# Serial.net
KiCad netlist of a schematic drawn in Altium Designer
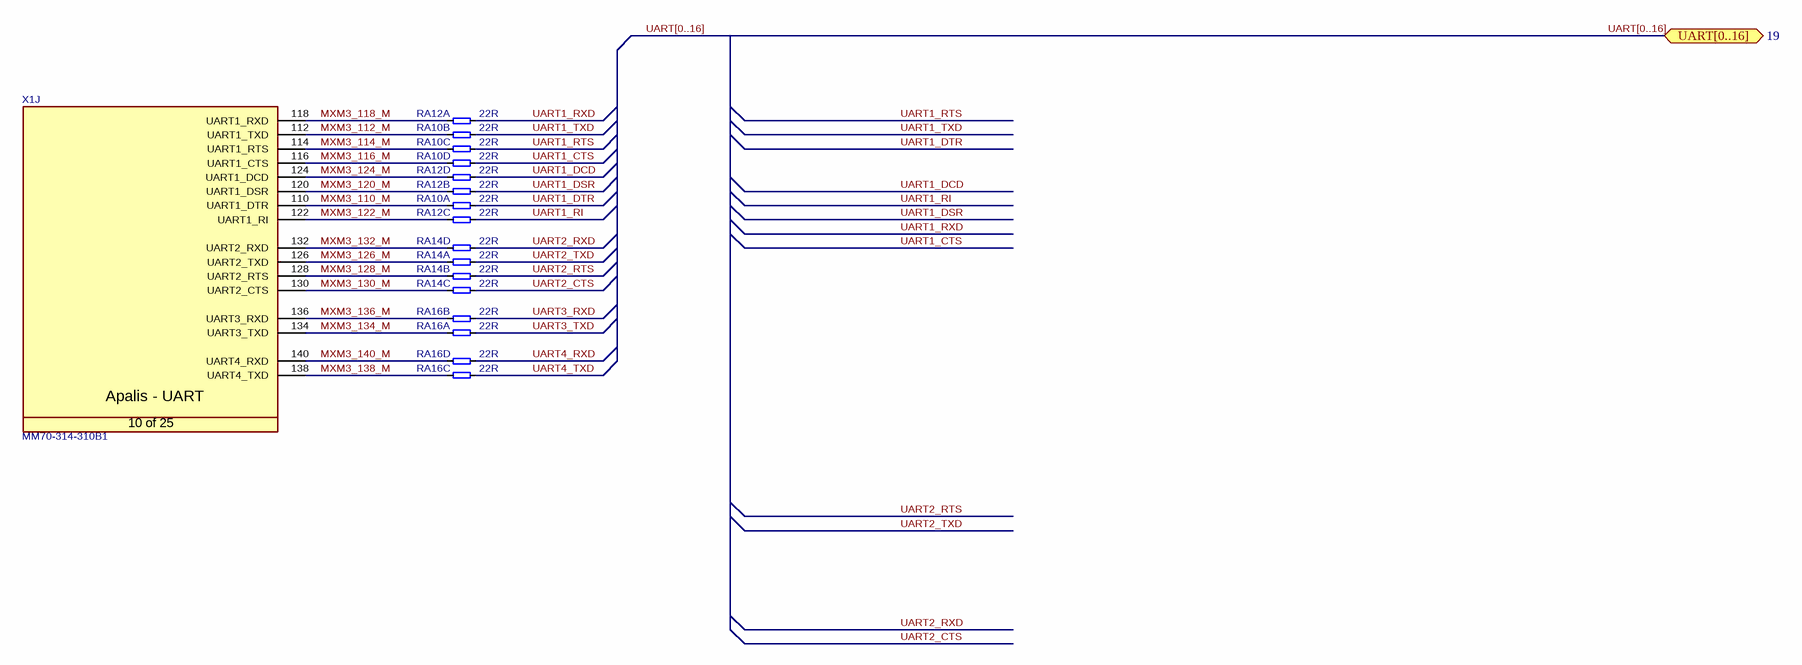
[diagram p0: Serial.SchDoc]

(export (version "E")
  (design (tool "Eeschema 10.0.6"))
  (components
    (comp (ref "RA10")
      (value "22R")
      (footprint "T_Resistor_Array_X4")
      (description "Resistor Array 22 R 63mW 5% 1206")
      (fields (field (name "TOLERANCE") "5%"))
      (libsource (lib "Ixora") (part "RA-22R-63mW-5%-1206-div"))
    )
    (comp (ref "RA12")
      (value "22R")
      (footprint "T_Resistor_Array_X4")
      (description "Resistor Array 22 R 63mW 5% 1206")
      (fields (field (name "TOLERANCE") "5%"))
      (libsource (lib "Ixora") (part "RA-22R-63mW-5%-1206-div"))
    )
    (comp (ref "RA14")
      (value "22R")
      (footprint "T_Resistor_Array_X4")
      (description "Resistor Array 22 R 63mW 5% 1206")
      (fields (field (name "TOLERANCE") "5%"))
      (libsource (lib "Ixora") (part "RA-22R-63mW-5%-1206-div"))
    )
    (comp (ref "RA16")
      (value "22R")
      (footprint "T_Resistor_Array_X4")
      (description "Resistor Array 22 R 63mW 5% 1206")
      (fields (field (name "TOLERANCE") "5%"))
      (libsource (lib "Ixora") (part "RA-22R-63mW-5%-1206-div"))
    )
    (comp (ref "X1")
      (value "CON-JAE-MM70-314-310B1-314-0.5mm")
      (footprint "T_JAE_MM70-314-310B1")
      (description "MXM3 Connector")
      (fields (field (name "MANUFACTURER PART NO.") "MM70-314-310B1"))
      (libsource (lib "Ixora") (part "CON-JAE-MM70-314-310B1-314-0.5mm"))
    )
  )
  (nets
    (net (code "18") (name "/MXM3_110_M") (class "Default")
      (node (ref "RA10") (pin "1") (pinfunction "1_1") (pintype "passive"))
      (node (ref "X1") (pin "110") (pinfunction "UART1_DTR_110") (pintype "passive"))
    )
    (net (code "19") (name "/MXM3_112_M") (class "Default")
      (node (ref "RA10") (pin "2") (pinfunction "2_2") (pintype "passive"))
      (node (ref "X1") (pin "112") (pinfunction "UART1_TXD_112") (pintype "passive"))
    )
    (net (code "20") (name "/MXM3_114_M") (class "Default")
      (node (ref "RA10") (pin "3") (pinfunction "3_3") (pintype "passive"))
      (node (ref "X1") (pin "114") (pinfunction "UART1_RTS_114") (pintype "passive"))
    )
    (net (code "21") (name "/MXM3_116_M") (class "Default")
      (node (ref "RA10") (pin "4") (pinfunction "4_4") (pintype "passive"))
      (node (ref "X1") (pin "116") (pinfunction "UART1_CTS_116") (pintype "passive"))
    )
    (net (code "23") (name "/MXM3_118_M") (class "Default")
      (node (ref "RA12") (pin "1") (pinfunction "1_1") (pintype "passive"))
      (node (ref "X1") (pin "118") (pinfunction "UART1_RXD_118") (pintype "passive"))
    )
    (net (code "24") (name "/MXM3_120_M") (class "Default")
      (node (ref "RA12") (pin "2") (pinfunction "2_2") (pintype "passive"))
      (node (ref "X1") (pin "120") (pinfunction "UART1_DSR_120") (pintype "passive"))
    )
    (net (code "25") (name "/MXM3_122_M") (class "Default")
      (node (ref "RA12") (pin "3") (pinfunction "3_3") (pintype "passive"))
      (node (ref "X1") (pin "122") (pinfunction "UART1_RI_122") (pintype "passive"))
    )
    (net (code "26") (name "/MXM3_124_M") (class "Default")
      (node (ref "RA12") (pin "4") (pinfunction "4_4") (pintype "passive"))
      (node (ref "X1") (pin "124") (pinfunction "UART1_DCD_124") (pintype "passive"))
    )
    (net (code "27") (name "/MXM3_126_M") (class "Default")
      (node (ref "RA14") (pin "1") (pinfunction "1_1") (pintype "passive"))
      (node (ref "X1") (pin "126") (pinfunction "UART2_TXD_126") (pintype "passive"))
    )
    (net (code "28") (name "/MXM3_128_M") (class "Default")
      (node (ref "RA14") (pin "2") (pinfunction "2_2") (pintype "passive"))
      (node (ref "X1") (pin "128") (pinfunction "UART2_RTS_128") (pintype "passive"))
    )
    (net (code "29") (name "/MXM3_130_M") (class "Default")
      (node (ref "RA14") (pin "3") (pinfunction "3_3") (pintype "passive"))
      (node (ref "X1") (pin "130") (pinfunction "UART2_CTS_130") (pintype "passive"))
    )
    (net (code "30") (name "/MXM3_132_M") (class "Default")
      (node (ref "RA14") (pin "4") (pinfunction "4_4") (pintype "passive"))
      (node (ref "X1") (pin "132") (pinfunction "UART2_RXD_132") (pintype "passive"))
    )
    (net (code "31") (name "/MXM3_134_M") (class "Default")
      (node (ref "RA16") (pin "1") (pinfunction "1_1") (pintype "passive"))
      (node (ref "X1") (pin "134") (pinfunction "UART3_TXD_134") (pintype "passive"))
    )
    (net (code "33") (name "/MXM3_136_M") (class "Default")
      (node (ref "RA16") (pin "2") (pinfunction "2_2") (pintype "passive"))
      (node (ref "X1") (pin "136") (pinfunction "UART3_RXD_136") (pintype "passive"))
    )
    (net (code "34") (name "/MXM3_138_M") (class "Default")
      (node (ref "RA16") (pin "3") (pinfunction "3_3") (pintype "passive"))
      (node (ref "X1") (pin "138") (pinfunction "UART4_TXD_138") (pintype "passive"))
    )
    (net (code "35") (name "/MXM3_140_M") (class "Default")
      (node (ref "RA16") (pin "4") (pinfunction "4_4") (pintype "passive"))
      (node (ref "X1") (pin "140") (pinfunction "UART4_RXD_140") (pintype "passive"))
    )
    (net (code "36") (name "/UART1_CTS") (class "Default")
      (node (ref "RA10") (pin "8") (pinfunction "8_8") (pintype "passive"))
    )
    (net (code "37") (name "/UART1_DCD") (class "Default")
      (node (ref "RA12") (pin "8") (pinfunction "8_8") (pintype "passive"))
    )
    (net (code "38") (name "/UART1_DSR") (class "Default")
      (node (ref "RA12") (pin "6") (pinfunction "6_6") (pintype "passive"))
    )
    (net (code "39") (name "/UART1_DTR") (class "Default")
      (node (ref "RA10") (pin "5") (pinfunction "5_5") (pintype "passive"))
    )
    (net (code "40") (name "/UART1_RI") (class "Default")
      (node (ref "RA12") (pin "7") (pinfunction "7_7") (pintype "passive"))
    )
    (net (code "41") (name "/UART1_RTS") (class "Default")
      (node (ref "RA10") (pin "7") (pinfunction "7_7") (pintype "passive"))
    )
    (net (code "42") (name "/UART1_RXD") (class "Default")
      (node (ref "RA12") (pin "5") (pinfunction "5_5") (pintype "passive"))
    )
    (net (code "43") (name "/UART1_TXD") (class "Default")
      (node (ref "RA10") (pin "6") (pinfunction "6_6") (pintype "passive"))
    )
    (net (code "44") (name "/UART2_CTS") (class "Default")
      (node (ref "RA14") (pin "7") (pinfunction "7_7") (pintype "passive"))
    )
    (net (code "45") (name "/UART2_RTS") (class "Default")
      (node (ref "RA14") (pin "6") (pinfunction "6_6") (pintype "passive"))
    )
    (net (code "46") (name "/UART2_RXD") (class "Default")
      (node (ref "RA14") (pin "8") (pinfunction "8_8") (pintype "passive"))
    )
    (net (code "47") (name "/UART2_TXD") (class "Default")
      (node (ref "RA14") (pin "5") (pinfunction "5_5") (pintype "passive"))
    )
    (net (code "48") (name "/UART3_RXD") (class "Default")
      (node (ref "RA16") (pin "6") (pinfunction "6_6") (pintype "passive"))
    )
    (net (code "49") (name "/UART3_TXD") (class "Default")
      (node (ref "RA16") (pin "5") (pinfunction "5_5") (pintype "passive"))
    )
    (net (code "51") (name "/UART4_RXD") (class "Default")
      (node (ref "RA16") (pin "8") (pinfunction "8_8") (pintype "passive"))
    )
    (net (code "52") (name "/UART4_TXD") (class "Default")
      (node (ref "RA16") (pin "7") (pinfunction "7_7") (pintype "passive"))
    )
  )
)
